# Dawn.net
KiCad netlist of a schematic drawn in Altium Designer
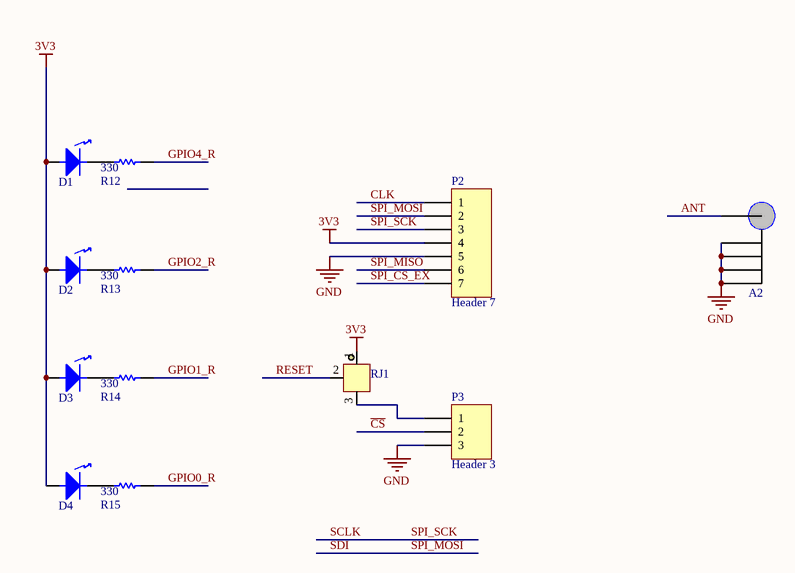
[diagram p0: Dawn.SchDoc]

(export (version "E")
  (design (tool "Eeschema 10.0.6"))
  (components
    (comp (ref "A2")
      (value "CONSMA003.062")
      (footprint "SMA_EDGE_MNT")
      (description "CONN SMA JACK 50 OHM EDGE MNT")
      (fields (field (name "MANUFACTURER") "Linx Technologies Inc"))
      (libsource (lib "DW1000Breakout") (part "CONSMA003.062"))
    )
    (comp (ref "D1")
      (value "LG Q971-KN-1")
      (footprint "CHIPLED0603")
      (description "LED CHIPLED 570NM GREEN 0603 SMD")
      (fields (field (name "MANUFACTURER") "OSRAM Opto Semiconductors Inc"))
      (libsource (lib "DWM1000Breakout") (part "LG Q971-KN-1"))
    )
    (comp (ref "D2")
      (value "LG Q971-KN-1")
      (footprint "CHIPLED0603")
      (description "LED CHIPLED 570NM GREEN 0603 SMD")
      (fields (field (name "MANUFACTURER") "OSRAM Opto Semiconductors Inc"))
      (libsource (lib "DWM1000Breakout") (part "LG Q971-KN-1"))
    )
    (comp (ref "D3")
      (value "LG Q971-KN-1")
      (footprint "CHIPLED0603")
      (description "LED CHIPLED 570NM GREEN 0603 SMD")
      (fields (field (name "MANUFACTURER") "OSRAM Opto Semiconductors Inc"))
      (libsource (lib "DWM1000Breakout") (part "LG Q971-KN-1"))
    )
    (comp (ref "D4")
      (value "LG Q971-KN-1")
      (footprint "CHIPLED0603")
      (description "LED CHIPLED 570NM GREEN 0603 SMD")
      (fields (field (name "MANUFACTURER") "OSRAM Opto Semiconductors Inc"))
      (libsource (lib "DWM1000Breakout") (part "LG Q971-KN-1"))
    )
    (comp (ref "P2")
      (value "Header 7")
      (footprint "HDR1X7")
      (description "Header, 7-Pin")
      (fields (field (name "PUBLISHER") "Altium Limited"))
      (libsource (lib "Miscellaneous Connectors") (part "Header 7"))
    )
    (comp (ref "P3")
      (value "Header 3")
      (footprint "HDR1X3")
      (description "Header, 3-Pin")
      (fields (field (name "PUBLISHER") "Altium Limited"))
      (libsource (lib "Miscellaneous Connectors") (part "Header 3"))
    )
    (comp (ref "R12")
      (value "MCR03ERTJ331")
      (footprint "RESC1608X06N (0603)")
      (description "RES 330 OHM 1/10W 5% 0603 SMD")
      (fields (field (name "MANUFACTURER") "Rohm Semiconductor") (field (name "TOLERANCE") "±5%"))
      (libsource (lib "Chronos") (part "MCR03ERTJ331"))
    )
    (comp (ref "R13")
      (value "MCR03ERTJ331")
      (footprint "RESC1608X06N (0603)")
      (description "RES 330 OHM 1/10W 5% 0603 SMD")
      (fields (field (name "MANUFACTURER") "Rohm Semiconductor") (field (name "TOLERANCE") "±5%"))
      (libsource (lib "Chronos") (part "MCR03ERTJ331"))
    )
    (comp (ref "R14")
      (value "MCR03ERTJ331")
      (footprint "RESC1608X06N (0603)")
      (description "RES 330 OHM 1/10W 5% 0603 SMD")
      (fields (field (name "MANUFACTURER") "Rohm Semiconductor") (field (name "TOLERANCE") "±5%"))
      (libsource (lib "Chronos") (part "MCR03ERTJ331"))
    )
    (comp (ref "R15")
      (value "MCR03ERTJ331")
      (footprint "RESC1608X06N (0603)")
      (description "RES 330 OHM 1/10W 5% 0603 SMD")
      (fields (field (name "MANUFACTURER") "Rohm Semiconductor") (field (name "TOLERANCE") "±5%"))
      (libsource (lib "Chronos") (part "MCR03ERTJ331"))
    )
    (comp (ref "RJ1")
      (value "R_J")
      (footprint "RJ")
      (description "Resistor Jumper")
      (libsource (lib "Chronos") (part "R_J"))
    )
  )
  (nets
    (net (code "1") (name "/ANT") (class "Default")
      (node (ref "A2") (pin "1") (pinfunction "1_1") (pintype "passive"))
    )
    (net (code "2") (name "/CLK") (class "Default")
      (node (ref "P2") (pin "1") (pinfunction "1_1") (pintype "passive"))
    )
    (net (code "3") (name "/GPIO0_R") (class "Default")
      (node (ref "R15") (pin "2") (pinfunction "2_2") (pintype "passive"))
    )
    (net (code "4") (name "/GPIO1_R") (class "Default")
      (node (ref "R14") (pin "2") (pinfunction "2_2") (pintype "passive"))
    )
    (net (code "5") (name "/GPIO2_R") (class "Default")
      (node (ref "R13") (pin "2") (pinfunction "2_2") (pintype "passive"))
    )
    (net (code "6") (name "/GPIO4_R") (class "Default")
      (node (ref "R12") (pin "2") (pinfunction "2_2") (pintype "passive"))
    )
    (net (code "7") (name "/RESET") (class "Default")
      (node (ref "RJ1") (pin "2") (pinfunction "2_2") (pintype "passive"))
    )
    (net (code "8") (name "/SCLK") (class "Default")
      (node (ref "P2") (pin "3") (pinfunction "3_3") (pintype "passive"))
    )
    (net (code "9") (name "/SDI") (class "Default")
      (node (ref "P2") (pin "2") (pinfunction "2_2") (pintype "passive"))
    )
    (net (code "10") (name "/SPI_CS_EX") (class "Default")
      (node (ref "P2") (pin "7") (pinfunction "7_7") (pintype "passive"))
    )
    (net (code "11") (name "/SPI_MISO") (class "Default")
      (node (ref "P2") (pin "6") (pinfunction "6_6") (pintype "passive"))
    )
    (net (code "12") (name "/~{CS}") (class "Default")
      (node (ref "P3") (pin "2") (pinfunction "2_2") (pintype "passive"))
    )
    (net (code "13") (name "3V3") (class "Default")
      (node (ref "D1") (pin "1") (pinfunction "1_1") (pintype "passive"))
      (node (ref "D2") (pin "1") (pinfunction "1_1") (pintype "passive"))
      (node (ref "D3") (pin "1") (pinfunction "1_1") (pintype "passive"))
      (node (ref "D4") (pin "1") (pinfunction "1_1") (pintype "passive"))
      (node (ref "P2") (pin "4") (pinfunction "4_4") (pintype "passive"))
      (node (ref "RJ1") (pin "1") (pinfunction "1_1") (pintype "passive"))
    )
    (net (code "14") (name "GND") (class "Default")
      (node (ref "A2") (pin "2") (pinfunction "2_2") (pintype "passive"))
      (node (ref "A2") (pin "3") (pinfunction "3_3") (pintype "passive"))
      (node (ref "A2") (pin "4") (pinfunction "4_4") (pintype "passive"))
      (node (ref "A2") (pin "5") (pinfunction "5_5") (pintype "passive"))
      (node (ref "P2") (pin "5") (pinfunction "5_5") (pintype "passive"))
      (node (ref "P3") (pin "3") (pinfunction "3_3") (pintype "passive"))
    )
    (net (code "15") (name "Net-(D1-Pad2)") (class "Default")
      (node (ref "D1") (pin "2") (pinfunction "2_2") (pintype "passive"))
      (node (ref "R12") (pin "1") (pinfunction "1_1") (pintype "passive"))
    )
    (net (code "16") (name "Net-(D2-Pad2)") (class "Default")
      (node (ref "D2") (pin "2") (pinfunction "2_2") (pintype "passive"))
      (node (ref "R13") (pin "1") (pinfunction "1_1") (pintype "passive"))
    )
    (net (code "17") (name "Net-(D3-Pad2)") (class "Default")
      (node (ref "D3") (pin "2") (pinfunction "2_2") (pintype "passive"))
      (node (ref "R14") (pin "1") (pinfunction "1_1") (pintype "passive"))
    )
    (net (code "18") (name "Net-(D4-Pad2)") (class "Default")
      (node (ref "D4") (pin "2") (pinfunction "2_2") (pintype "passive"))
      (node (ref "R15") (pin "1") (pinfunction "1_1") (pintype "passive"))
    )
    (net (code "19") (name "Net-(P3-Pad1)") (class "Default")
      (node (ref "P3") (pin "1") (pinfunction "1_1") (pintype "passive"))
      (node (ref "RJ1") (pin "3") (pinfunction "3_3") (pintype "passive"))
    )
  )
)
